# CAN.net
KiCad netlist of a schematic drawn in Altium Designer
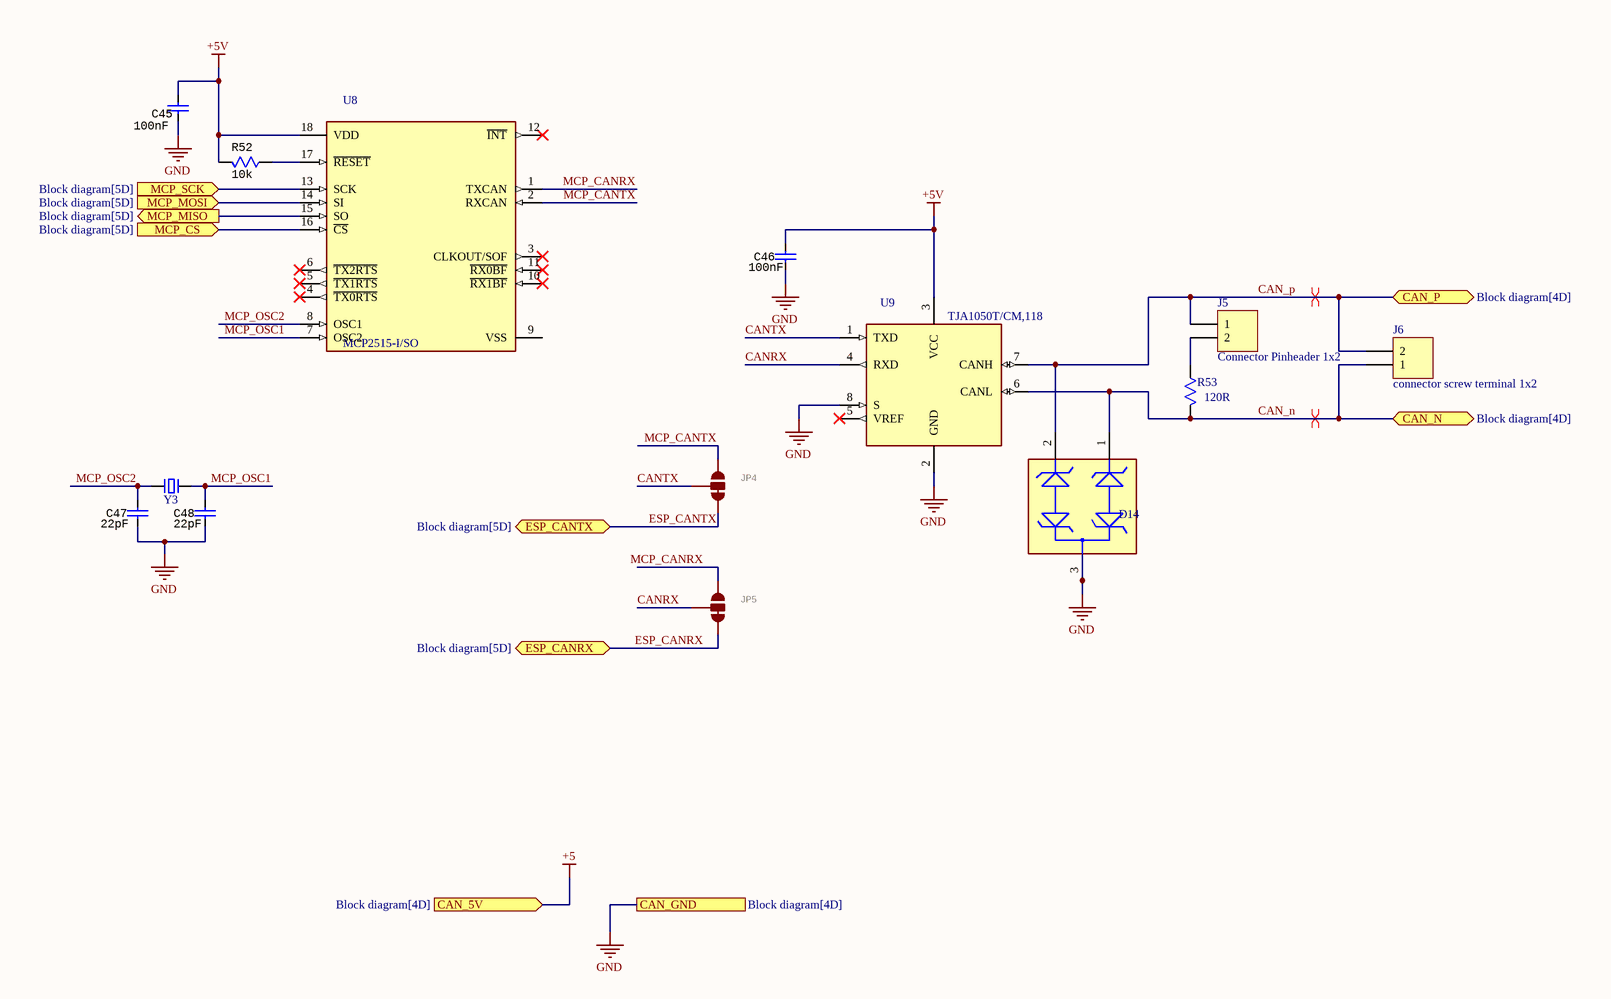
[diagram p0: CAN.SchDoc]

(export (version "E")
  (design (tool "Eeschema 10.0.6"))
  (components
    (comp (ref "C45")
      (value "100nF")
      (footprint "CAP Ceramic SMD 0603")
      (description "Multilayer Ceramic Capacitors MLCC Surface Mount 0603 0.1uF 50 Volts X7R 10%")
      (fields
        (field (name "MANUFACTURER") "Murata")
        (field (name "MANUFACTURER PART NUMBER") "GRM188R71H104KA93D")
      )
      (libsource (lib "Passive") (part "CAP 0603 100nF 50V"))
    )
    (comp (ref "C46")
      (value "100nF")
      (footprint "CAP Ceramic SMD 0603")
      (description "Multilayer Ceramic Capacitors MLCC Surface Mount 0603 0.1uF 50 Volts X7R 10%")
      (fields
        (field (name "MANUFACTURER") "Murata")
        (field (name "MANUFACTURER PART NUMBER") "GRM188R71H104KA93D")
      )
      (libsource (lib "Passive") (part "CAP 0603 100nF 50V"))
    )
    (comp (ref "C47")
      (value "22pF")
      (footprint "CAP Ceramic SMD 0603")
      (description "CAP CER 22PF 50V C0G/NP0 0603")
      (fields
        (field (name "MANUFACTURER") "Samsung")
        (field (name "MANUFACTURER PART NUMBER") "CL10C220JB81PNC")
      )
      (libsource (lib "Passive") (part "CAP 0603 22pF 50V"))
    )
    (comp (ref "C48")
      (value "22pF")
      (footprint "CAP Ceramic SMD 0603")
      (description "CAP CER 22PF 50V C0G/NP0 0603")
      (fields
        (field (name "MANUFACTURER") "Samsung")
        (field (name "MANUFACTURER PART NUMBER") "CL10C220JB81PNC")
      )
      (libsource (lib "Passive") (part "CAP 0603 22pF 50V"))
    )
    (comp (ref "D14")
      (value "CPDT_12V")
      (footprint "SOT23")
      (description "TVS DIODE SOT23-3 (CAN TVS)")
      (fields
        (field (name "MANUFACTURER") "Bourns Inc.")
        (field (name "MANUFACTURER PART NUMBER") "CDSOT23-SM712")
      )
      (libsource (lib "diode") (part "CPDT_12V"))
    )
    (comp (ref "J5")
      (value "Connector Pinheader 1x2")
      (footprint "Header 1.27X2")
      (description "Header_2x1")
      (libsource (lib "Signal connectors") (part "Connector Pinheader 1x2"))
    )
    (comp (ref "J6")
      (value "connector screw terminal 1x2")
      (footprint "Connector screw terminal Block TH 1x2 3.5")
      (description "691214110002 - Wire-To-Board Terminal Block, 3.5 mm, 2 Positions, 24 AWG, 16 AWG, 1.5 mm², Screw")
      (fields
        (field (name "MANUFACTURER") "Wurth Electronics")
        (field (name "MANUFACTURER PART NUMBER") "691214110002")
      )
      (libsource (lib "Power connectors") (part "connector screw terminal 1x2"))
    )
    (comp (ref "JP4")
      (value "JUMPER-SMT_3_1-NC_TRACE_SILK")
      (footprint "SMT-JUMPER_3_1-NC_TRACE_SILK")
      (libsource (lib "Bypass, Testpoint and Holes") (part "JUMPER-SMT_3_1-NC_TRACE_SILK"))
    )
    (comp (ref "JP5")
      (value "JUMPER-SMT_3_1-NC_TRACE_SILK")
      (footprint "SMT-JUMPER_3_1-NC_TRACE_SILK")
      (libsource (lib "Bypass, Testpoint and Holes") (part "JUMPER-SMT_3_1-NC_TRACE_SILK"))
    )
    (comp (ref "R52")
      (value "10k")
      (footprint "RES SMD 0603")
      (description "Res Thick Film 0603 10K Ohm 1% 1/10W ±100ppm/°C Molded SMD Punched Carrier T/R")
      (fields (field (name "TOLERANCE") "1%") (field (name "MANUFACTURER") "Panasonic"))
      (libsource (lib "Passive") (part "RES 0603 10k 1%"))
    )
    (comp (ref "R53")
      (value "120R")
      (footprint "RES SMD 0603")
      (description "Res General Purpose Thick Film 0603 120 Ohm 1% 1/10W ±100ppm/°C Molded SMD Paper T/R")
      (fields (field (name "TOLERANCE") "1%") (field (name "RESISTANCE") "120R"))
      (libsource (lib "Passive") (part "RES 0603 120R 1%"))
    )
    (comp (ref "U8")
      (value "MCP2515-I/SO")
      (footprint "MCP2515")
      (description "IC CAN CONTROLLER W/SPI 18SOIC")
      (fields (field (name "MANUFACTURER") "Microchip"))
      (libsource (lib "Communictation ICs") (part "MCP2515-I/SO"))
    )
    (comp (ref "U9")
      (value "TJA1050T/CM,118")
      (footprint "TJA1050T/CM,118")
      (description "1/1 Transceiver Half CANbus 8-SO")
      (fields (field (name "MANUFACTURER") "NXP USA"))
      (libsource (lib "Communictation ICs") (part "TJA1050T/CM,118"))
    )
    (comp (ref "Y3")
      (value "X49SD8MSD2SC")
      (footprint "Crystal TH 2-PIN HC-49S")
      (description "8MHz 49S Crystals 20pF ±20ppm ±30ppm -20℃~+70℃ HC-49S Crystals ROHS")
      (libsource (lib "Crystal") (part "X49SD8MSD2SC"))
    )
  )
  (nets
    (net (code "2") (name "+5V") (class "Default")
      (node (ref "C45") (pin "2") (pinfunction "2_2") (pintype "passive"))
      (node (ref "C46") (pin "2") (pinfunction "2_2") (pintype "passive"))
      (node (ref "R52") (pin "2") (pinfunction "2_2") (pintype "passive"))
      (node (ref "U8") (pin "18") (pinfunction "VDD_18") (pintype "power_in"))
      (node (ref "U9") (pin "3") (pinfunction "VCC_3") (pintype "power_in"))
    )
    (net (code "3") (name "/CANRX") (class "Default")
      (node (ref "JP5") (pin "2") (pinfunction "2_2") (pintype "passive"))
      (node (ref "U9") (pin "4") (pinfunction "RXD_4") (pintype "output"))
    )
    (net (code "4") (name "/CANTX") (class "Default")
      (node (ref "JP4") (pin "2") (pinfunction "2_2") (pintype "passive"))
      (node (ref "U9") (pin "1") (pinfunction "TXD_1") (pintype "input"))
    )
    (net (code "5") (name "/CAN_n") (class "Default")
      (node (ref "D14") (pin "1") (pinfunction "1_1") (pintype "passive"))
      (node (ref "J6") (pin "1") (pinfunction "1_1") (pintype "passive"))
      (node (ref "R53") (pin "2") (pinfunction "2_2") (pintype "passive"))
      (node (ref "U9") (pin "6") (pinfunction "CANL_6") (pintype "bidirectional"))
    )
    (net (code "6") (name "/CAN_p") (class "Default")
      (node (ref "D14") (pin "2") (pinfunction "2_2") (pintype "passive"))
      (node (ref "J5") (pin "1") (pinfunction "1_1") (pintype "passive"))
      (node (ref "J6") (pin "2") (pinfunction "2_2") (pintype "passive"))
      (node (ref "U9") (pin "7") (pinfunction "CANH_7") (pintype "bidirectional"))
    )
    (net (code "7") (name "/ESP_CANRX") (class "Default")
      (node (ref "JP5") (pin "3") (pinfunction "3_3") (pintype "passive"))
    )
    (net (code "8") (name "/ESP_CANTX") (class "Default")
      (node (ref "JP4") (pin "3") (pinfunction "3_3") (pintype "passive"))
    )
    (net (code "9") (name "/MCP_CANRX") (class "Default")
      (node (ref "JP5") (pin "1") (pinfunction "1_1") (pintype "passive"))
      (node (ref "U8") (pin "1") (pinfunction "TXCAN_1") (pintype "output"))
    )
    (net (code "10") (name "/MCP_CANTX") (class "Default")
      (node (ref "JP4") (pin "1") (pinfunction "1_1") (pintype "passive"))
      (node (ref "U8") (pin "2") (pinfunction "RXCAN_2") (pintype "input"))
    )
    (net (code "11") (name "/MCP_CS") (class "Default")
      (node (ref "U8") (pin "16") (pinfunction "~{CS}_16") (pintype "input"))
    )
    (net (code "12") (name "/MCP_MISO") (class "Default")
      (node (ref "U8") (pin "15") (pinfunction "SO_15") (pintype "input"))
    )
    (net (code "13") (name "/MCP_MOSI") (class "Default")
      (node (ref "U8") (pin "14") (pinfunction "SI_14") (pintype "input"))
    )
    (net (code "14") (name "/MCP_OSC1") (class "Default")
      (node (ref "C48") (pin "2") (pinfunction "2_2") (pintype "passive"))
      (node (ref "U8") (pin "7") (pinfunction "OSC2_7") (pintype "input"))
      (node (ref "Y3") (pin "1") (pinfunction "1_1") (pintype "passive"))
    )
    (net (code "15") (name "/MCP_OSC2") (class "Default")
      (node (ref "C47") (pin "2") (pinfunction "2_2") (pintype "passive"))
      (node (ref "U8") (pin "8") (pinfunction "OSC1_8") (pintype "input"))
      (node (ref "Y3") (pin "2") (pinfunction "2_2") (pintype "passive"))
    )
    (net (code "16") (name "/MCP_SCK") (class "Default")
      (node (ref "U8") (pin "13") (pinfunction "SCK_13") (pintype "input"))
    )
    (net (code "17") (name "GND") (class "Default")
      (node (ref "C45") (pin "1") (pinfunction "1_1") (pintype "passive"))
      (node (ref "C46") (pin "1") (pinfunction "1_1") (pintype "passive"))
      (node (ref "C47") (pin "1") (pinfunction "1_1") (pintype "passive"))
      (node (ref "C48") (pin "1") (pinfunction "1_1") (pintype "passive"))
      (node (ref "D14") (pin "3") (pinfunction "3_3") (pintype "passive"))
      (node (ref "U9") (pin "2") (pinfunction "GND_2") (pintype "power_in"))
      (node (ref "U9") (pin "8") (pinfunction "S_8") (pintype "input"))
    )
    (net (code "18") (name "Net-(J5-Pad2)") (class "Default")
      (node (ref "J5") (pin "2") (pinfunction "2_2") (pintype "passive"))
      (node (ref "R53") (pin "1") (pinfunction "1_1") (pintype "passive"))
    )
    (net (code "19") (name "Net-(U8-~{RESET})") (class "Default")
      (node (ref "R52") (pin "1") (pinfunction "1_1") (pintype "passive"))
      (node (ref "U8") (pin "17") (pinfunction "~{RESET}_17") (pintype "input"))
    )
    (net (code "20") (name "unconnected-(U8-CLKOUT{slash}SOF-Pad3)") (class "Default")
      (node (ref "U8") (pin "3") (pinfunction "CLKOUT/SOF_3") (pintype "output+no_connect"))
    )
    (net (code "21") (name "unconnected-(U8-VSS-Pad9)") (class "Default")
      (node (ref "U8") (pin "9") (pinfunction "VSS_9") (pintype "power_in"))
    )
    (net (code "22") (name "unconnected-(U8-~{INT}-Pad12)") (class "Default")
      (node (ref "U8") (pin "12") (pinfunction "~{INT}_12") (pintype "output+no_connect"))
    )
    (net (code "23") (name "unconnected-(U8-~{RX0BF}-Pad11)") (class "Default")
      (node (ref "U8") (pin "11") (pinfunction "~{RX0BF}_11") (pintype "input+no_connect"))
    )
    (net (code "24") (name "unconnected-(U8-~{RX1BF}-Pad10)") (class "Default")
      (node (ref "U8") (pin "10") (pinfunction "~{RX1BF}_10") (pintype "input+no_connect"))
    )
    (net (code "25") (name "unconnected-(U8-~{TX0RTS}-Pad4)") (class "Default")
      (node (ref "U8") (pin "4") (pinfunction "~{TX0RTS}_4") (pintype "output+no_connect"))
    )
    (net (code "26") (name "unconnected-(U8-~{TX1RTS}-Pad5)") (class "Default")
      (node (ref "U8") (pin "5") (pinfunction "~{TX1RTS}_5") (pintype "output+no_connect"))
    )
    (net (code "27") (name "unconnected-(U8-~{TX2RTS}-Pad6)") (class "Default")
      (node (ref "U8") (pin "6") (pinfunction "~{TX2RTS}_6") (pintype "output+no_connect"))
    )
    (net (code "28") (name "unconnected-(U9-VREF-Pad5)") (class "Default")
      (node (ref "U9") (pin "5") (pinfunction "VREF_5") (pintype "output+no_connect"))
    )
  )
)
